# other.net
KiCad netlist of a schematic drawn in Altium Designer
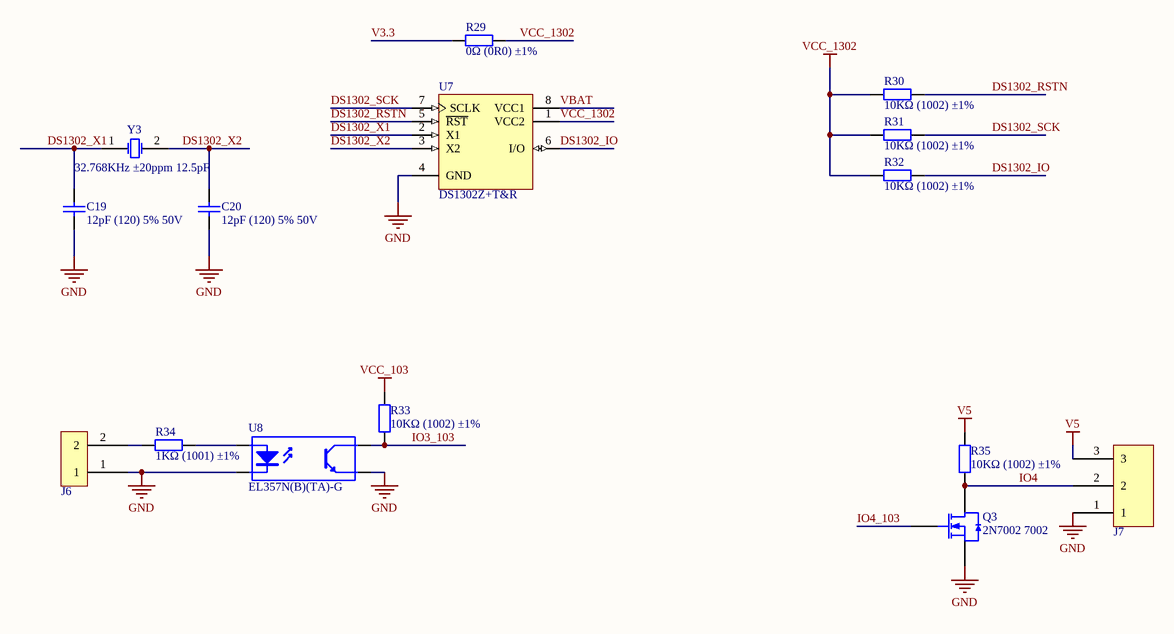
[diagram p0: other.SchDoc]

(export (version "E")
  (design (tool "Eeschema 10.0.6"))
  (components
    (comp (ref "C19")
      (value "12pF (120) 5% 50V")
      (footprint "0603_C")
      (description "贴片电容")
      (libsource (lib "Miscellaneous Devices LC") (part "0603 12pF (120) 5% 50V"))
    )
    (comp (ref "C20")
      (value "12pF (120) 5% 50V")
      (footprint "0603_C")
      (description "贴片电容")
      (libsource (lib "Miscellaneous Devices LC") (part "0603 12pF (120) 5% 50V"))
    )
    (comp (ref "J6") (value "KF301-2P") (footprint "KF301-2P") (libsource (lib "CHK-I") (part "KF301-2P")))
    (comp (ref "J7") (value "KF301-3P") (footprint "KF301-3P") (libsource (lib "CHK-I") (part "KF301-3P")))
    (comp (ref "Q3")
      (value "2N7002 7002")
      (footprint "SOT-23(SOT-23-3)")
      (description "MOS(场效应管)")
      (libsource (lib "Miscellaneous Devices LC") (part "2N7002 7002"))
    )
    (comp (ref "R29")
      (value "0Ω (0R0) ±1%")
      (footprint "1206_R")
      (description "贴片电阻")
      (libsource (lib "Miscellaneous Devices LC") (part "1206 0Ω (0R0) 1%"))
    )
    (comp (ref "R30")
      (value "10KΩ (1002) ±1%")
      (footprint "0603_R")
      (description "贴片电阻")
      (libsource (lib "Miscellaneous Devices LC") (part "0603 10KΩ (1002) 1%"))
    )
    (comp (ref "R31")
      (value "10KΩ (1002) ±1%")
      (footprint "0603_R")
      (description "贴片电阻")
      (libsource (lib "Miscellaneous Devices LC") (part "0603 10KΩ (1002) 1%"))
    )
    (comp (ref "R32")
      (value "10KΩ (1002) ±1%")
      (footprint "0603_R")
      (description "贴片电阻")
      (libsource (lib "Miscellaneous Devices LC") (part "0603 10KΩ (1002) 1%"))
    )
    (comp (ref "R33")
      (value "10KΩ (1002) ±1%")
      (footprint "1206_R")
      (description "贴片电阻")
      (libsource (lib "Miscellaneous Devices LC") (part "1206 10KΩ (1002) 1%"))
    )
    (comp (ref "R34")
      (value "1KΩ (1001) ±1%")
      (footprint "1206_R")
      (description "贴片电阻")
      (libsource (lib "Miscellaneous Devices LC") (part "1206 1KΩ (1001) 1%"))
    )
    (comp (ref "R35")
      (value "10KΩ (1002) ±1%")
      (footprint "1206_R")
      (description "贴片电阻")
      (libsource (lib "Miscellaneous Devices LC") (part "1206 10KΩ (1002) 1%"))
    )
    (comp (ref "U7")
      (value "DS1302Z+T&R")
      (footprint "SOIC-8_150mil")
      (description "实时时钟")
      (libsource (lib "Miscellaneous Devices LC") (part "DS1302Z+T&R_[C8959]"))
    )
    (comp (ref "U8")
      (value "EL357N(B)(TA)-G")
      (footprint "SOP-4_P2.54")
      (description "贴片光耦")
      (libsource (lib "Miscellaneous Devices LC") (part "EL357N(B)(TA)-G_[C6649]"))
    )
    (comp (ref "Y3")
      (value "32.768KHz ±20ppm 12.5pF")
      (footprint "SMD-3215_2P FC - 135")
      (description "贴片晶振")
      (libsource (lib "Miscellaneous Devices LC") (part "SMD-3215_2P 32.768KHz 20ppm 12.5pF"))
    )
  )
  (nets
    (net (code "1") (name "/DS1302_IO") (class "Default")
      (node (ref "R32") (pin "2") (pinfunction "2_2") (pintype "passive"))
      (node (ref "U7") (pin "6") (pinfunction "I/O_6") (pintype "bidirectional"))
    )
    (net (code "2") (name "/DS1302_RSTN") (class "Default")
      (node (ref "R30") (pin "2") (pinfunction "2_2") (pintype "passive"))
      (node (ref "U7") (pin "5") (pinfunction "~{RST}_5") (pintype "input"))
    )
    (net (code "3") (name "/DS1302_SCK") (class "Default")
      (node (ref "R31") (pin "2") (pinfunction "2_2") (pintype "passive"))
      (node (ref "U7") (pin "7") (pinfunction "SCLK_7") (pintype "input"))
    )
    (net (code "4") (name "/DS1302_X1") (class "Default")
      (node (ref "C19") (pin "2") (pinfunction "2_2") (pintype "passive"))
      (node (ref "U7") (pin "2") (pinfunction "X1_2") (pintype "input"))
      (node (ref "Y3") (pin "1") (pinfunction "OSC1_1") (pintype "passive"))
    )
    (net (code "5") (name "/DS1302_X2") (class "Default")
      (node (ref "C20") (pin "2") (pinfunction "2_2") (pintype "passive"))
      (node (ref "U7") (pin "3") (pinfunction "X2_3") (pintype "input"))
      (node (ref "Y3") (pin "2") (pinfunction "OSC2_2") (pintype "passive"))
    )
    (net (code "6") (name "/IO3_103") (class "Default")
      (node (ref "R33") (pin "1") (pinfunction "1_1") (pintype "passive"))
      (node (ref "U8") (pin "4") (pinfunction "C_4") (pintype "passive"))
    )
    (net (code "7") (name "/IO4") (class "Default")
      (node (ref "J7") (pin "2") (pinfunction "2_2") (pintype "passive"))
      (node (ref "Q3") (pin "3") (pinfunction "D_3") (pintype "passive"))
      (node (ref "R35") (pin "1") (pinfunction "1_1") (pintype "passive"))
    )
    (net (code "8") (name "/IO4_103") (class "Default")
      (node (ref "Q3") (pin "1") (pinfunction "G_1") (pintype "passive"))
    )
    (net (code "9") (name "/V3.3") (class "Default")
      (node (ref "R29") (pin "1") (pinfunction "1_1") (pintype "passive"))
    )
    (net (code "10") (name "/VBAT") (class "Default")
      (node (ref "U7") (pin "8") (pinfunction "VCC1_8") (pintype "power_in"))
    )
    (net (code "11") (name "GND") (class "Default")
      (node (ref "C19") (pin "1") (pinfunction "1_1") (pintype "passive"))
      (node (ref "C20") (pin "1") (pinfunction "1_1") (pintype "passive"))
      (node (ref "J6") (pin "1") (pinfunction "1_1") (pintype "passive"))
      (node (ref "J7") (pin "1") (pinfunction "1_1") (pintype "passive"))
      (node (ref "Q3") (pin "2") (pinfunction "S_2") (pintype "passive"))
      (node (ref "U7") (pin "4") (pinfunction "GND_4") (pintype "power_in"))
      (node (ref "U8") (pin "2") (pinfunction "K_2") (pintype "passive"))
      (node (ref "U8") (pin "3") (pinfunction "E_3") (pintype "passive"))
    )
    (net (code "12") (name "Net-(J6-Pad2)") (class "Default")
      (node (ref "J6") (pin "2") (pinfunction "2_2") (pintype "passive"))
      (node (ref "R34") (pin "1") (pinfunction "1_1") (pintype "passive"))
    )
    (net (code "13") (name "Net-(U8-A)") (class "Default")
      (node (ref "R34") (pin "2") (pinfunction "2_2") (pintype "passive"))
      (node (ref "U8") (pin "1") (pinfunction "A_1") (pintype "passive"))
    )
    (net (code "14") (name "V5") (class "Default")
      (node (ref "J7") (pin "3") (pinfunction "3_3") (pintype "passive"))
      (node (ref "R35") (pin "2") (pinfunction "2_2") (pintype "passive"))
    )
    (net (code "15") (name "VCC_103") (class "Default")
      (node (ref "R33") (pin "2") (pinfunction "2_2") (pintype "passive"))
    )
    (net (code "16") (name "VCC_1302") (class "Default")
      (node (ref "R29") (pin "2") (pinfunction "2_2") (pintype "passive"))
      (node (ref "R30") (pin "1") (pinfunction "1_1") (pintype "passive"))
      (node (ref "R31") (pin "1") (pinfunction "1_1") (pintype "passive"))
      (node (ref "R32") (pin "1") (pinfunction "1_1") (pintype "passive"))
      (node (ref "U7") (pin "1") (pinfunction "VCC2_1") (pintype "power_in"))
    )
  )
)
